# Breakout2v2.net
KiCad netlist of a schematic drawn in EAGLE
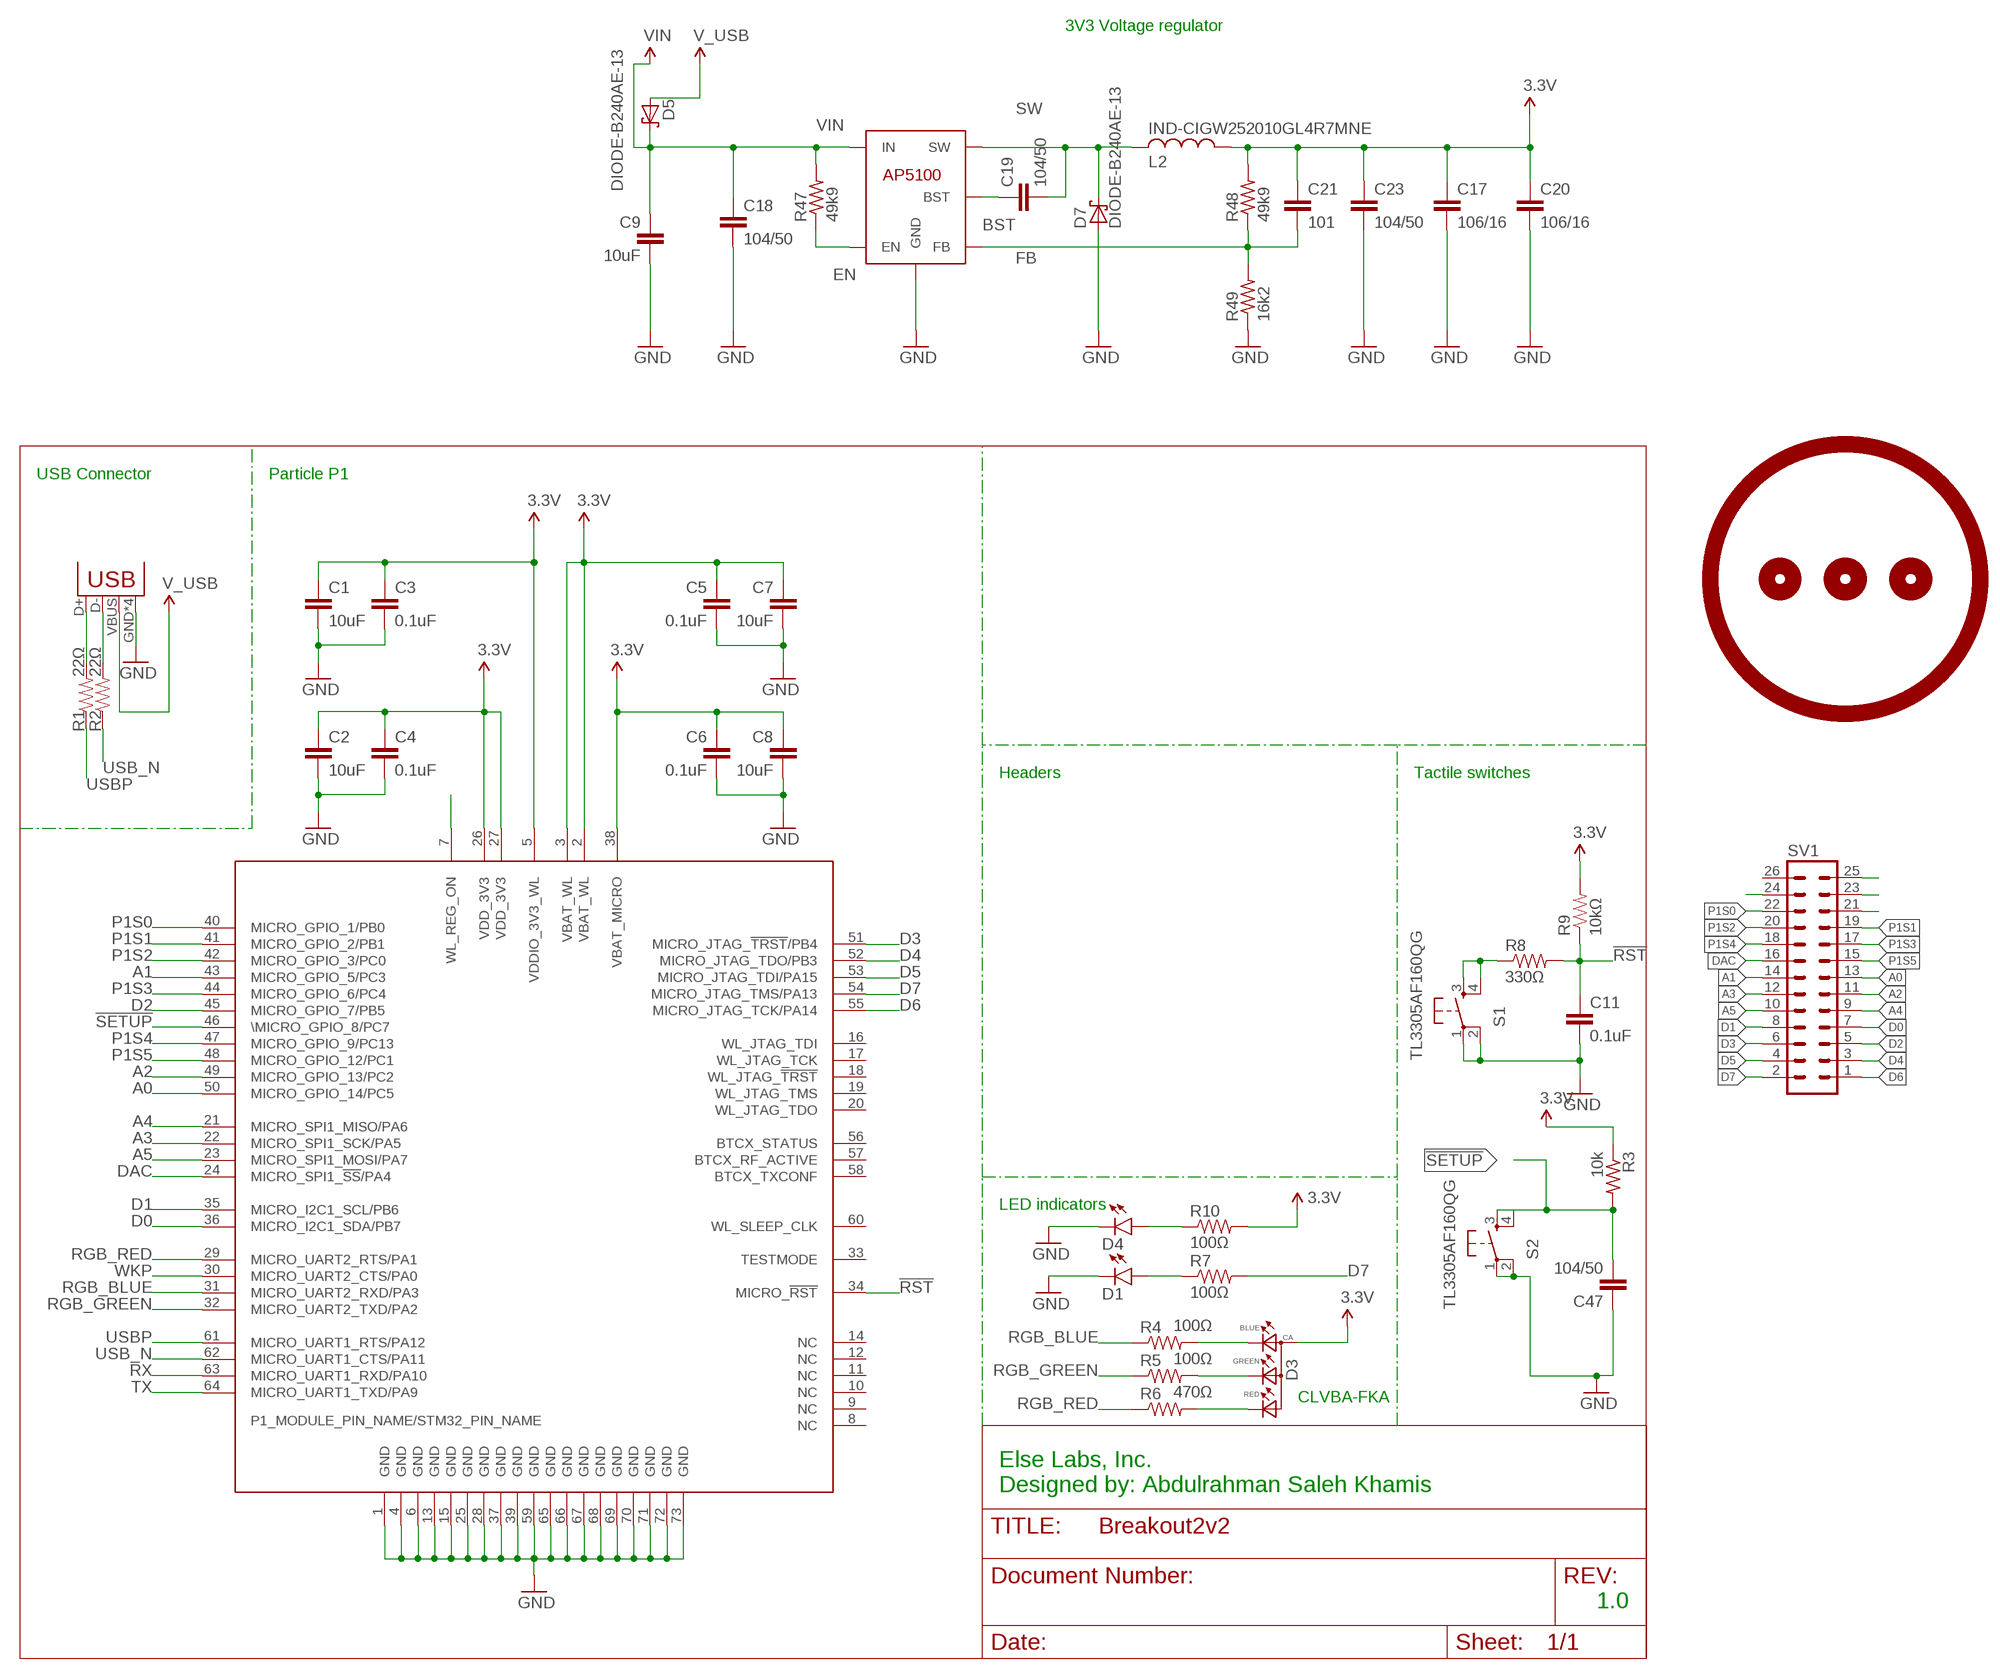
[diagram p0: schematic, sheet 1]

(export (version "E")
  (design (tool "Eeschema 10.0.6"))
  (components
    (comp (ref "C1")
      (value "10uF")
      (footprint "eagle-import:0805")
      (libsource (lib "eagle-import") (part "CAP0805"))
    )
    (comp (ref "C2")
      (value "10uF")
      (footprint "eagle-import:0805")
      (libsource (lib "eagle-import") (part "CAP0805"))
    )
    (comp (ref "C3")
      (value "0.1uF")
      (footprint "eagle-import:0805")
      (libsource (lib "eagle-import") (part "CAP0805"))
    )
    (comp (ref "C4")
      (value "0.1uF")
      (footprint "eagle-import:0805")
      (libsource (lib "eagle-import") (part "CAP0805"))
    )
    (comp (ref "C5")
      (value "0.1uF")
      (footprint "eagle-import:0805")
      (libsource (lib "eagle-import") (part "CAP0805"))
    )
    (comp (ref "C6")
      (value "0.1uF")
      (footprint "eagle-import:0805")
      (libsource (lib "eagle-import") (part "CAP0805"))
    )
    (comp (ref "C7")
      (value "10uF")
      (footprint "eagle-import:0805")
      (libsource (lib "eagle-import") (part "CAP0805"))
    )
    (comp (ref "C8")
      (value "10uF")
      (footprint "eagle-import:0805")
      (libsource (lib "eagle-import") (part "CAP0805"))
    )
    (comp (ref "C9")
      (value "10uF")
      (footprint "eagle-import:0805")
      (libsource (lib "eagle-import") (part "CAP0805"))
    )
    (comp (ref "C11")
      (value "0.1uF")
      (footprint "eagle-import:0805")
      (libsource (lib "eagle-import") (part "CAP0805"))
    )
    (comp (ref "C17")
      (value "106/16")
      (footprint "eagle-import:C0805")
      (libsource (lib "eagle-import") (part "C-EUC0805"))
    )
    (comp (ref "C18")
      (value "104/50")
      (footprint "eagle-import:C0603")
      (libsource (lib "eagle-import") (part "C-EUC0603"))
    )
    (comp (ref "C19")
      (value "104/50")
      (footprint "eagle-import:C0603")
      (libsource (lib "eagle-import") (part "C-EUC0603"))
    )
    (comp (ref "C20")
      (value "106/16")
      (footprint "eagle-import:C0805")
      (libsource (lib "eagle-import") (part "C-EUC0805"))
    )
    (comp (ref "C21")
      (value "101")
      (footprint "eagle-import:C0603")
      (libsource (lib "eagle-import") (part "C-EUC0603"))
    )
    (comp (ref "C23")
      (value "104/50")
      (footprint "eagle-import:C0603")
      (libsource (lib "eagle-import") (part "C-EUC0603"))
    )
    (comp (ref "C47")
      (value "104/50")
      (footprint "eagle-import:C0603")
      (libsource (lib "eagle-import") (part "C-EUC0603"))
    )
    (comp (ref "D1")
      (value "LED0603")
      (footprint "eagle-import:LED-0603")
      (libsource (lib "eagle-import") (part "LED0603"))
    )
    (comp (ref "D3")
      (value "CLVBA-FKAPLCC")
      (footprint "eagle-import:4-PLCC")
      (libsource (lib "eagle-import") (part "CLVBA-FKAPLCC"))
    )
    (comp (ref "D4")
      (value "LED0603")
      (footprint "eagle-import:LED-0603")
      (libsource (lib "eagle-import") (part "LED0603"))
    )
    (comp (ref "D5")
      (value "DIODE-B240AE-13")
      (footprint "eagle-import:DO-214AC")
      (libsource (lib "eagle-import") (part "DIODE-B240AE-13"))
    )
    (comp (ref "D7")
      (value "DIODE-B240AE-13")
      (footprint "eagle-import:DO-214AC")
      (libsource (lib "eagle-import") (part "DIODE-B240AE-13"))
    )
    (comp (ref "IC5")
      (value "SMSP-BUCK-AP5100")
      (footprint "eagle-import:SOT23-6")
      (libsource (lib "eagle-import") (part "SMSP-BUCK-AP5100"))
    )
    (comp (ref "JP1")
      (value "USBUSB-MICROB-SLOT-HOLE")
      (footprint "eagle-import:USB-MICROB-SLOT-HOLE")
      (libsource (lib "eagle-import") (part "USBUSB-MICROB-SLOT-HOLE"))
    )
    (comp (ref "L2")
      (value "IND-CIGW252010GL4R7MNE")
      (footprint "eagle-import:L2520")
      (libsource (lib "eagle-import") (part "IND-CIGW252010GL4R7MNE"))
    )
    (comp (ref "R1")
      (value "22Ω")
      (footprint "eagle-import:0805")
      (libsource (lib "eagle-import") (part "RESISTOR0805-RES"))
    )
    (comp (ref "R2")
      (value "22Ω")
      (footprint "eagle-import:0805")
      (libsource (lib "eagle-import") (part "RESISTOR0805-RES"))
    )
    (comp (ref "R3")
      (value "10k")
      (footprint "eagle-import:R0603")
      (libsource (lib "eagle-import") (part "R-US_R0603"))
    )
    (comp (ref "R4")
      (value "100Ω")
      (footprint "eagle-import:0805")
      (libsource (lib "eagle-import") (part "RESISTOR0805-RES"))
    )
    (comp (ref "R5")
      (value "100Ω")
      (footprint "eagle-import:0805")
      (libsource (lib "eagle-import") (part "RESISTOR0805-RES"))
    )
    (comp (ref "R6")
      (value "470Ω")
      (footprint "eagle-import:0805")
      (libsource (lib "eagle-import") (part "RESISTOR0805-RES"))
    )
    (comp (ref "R7")
      (value "100Ω")
      (footprint "eagle-import:0805")
      (libsource (lib "eagle-import") (part "RESISTOR0805-RES"))
    )
    (comp (ref "R8")
      (value "330Ω")
      (footprint "eagle-import:0805")
      (libsource (lib "eagle-import") (part "RESISTOR0805-RES"))
    )
    (comp (ref "R9")
      (value "10kΩ")
      (footprint "eagle-import:0805")
      (libsource (lib "eagle-import") (part "RESISTOR0805-RES"))
    )
    (comp (ref "R10")
      (value "100Ω")
      (footprint "eagle-import:0805")
      (libsource (lib "eagle-import") (part "RESISTOR0805-RES"))
    )
    (comp (ref "R47")
      (value "49k9")
      (footprint "eagle-import:R0603")
      (libsource (lib "eagle-import") (part "R-US_R0603"))
    )
    (comp (ref "R48")
      (value "49k9")
      (footprint "eagle-import:R0603")
      (libsource (lib "eagle-import") (part "R-US_R0603"))
    )
    (comp (ref "R49")
      (value "16k2")
      (footprint "eagle-import:R0603")
      (libsource (lib "eagle-import") (part "R-US_R0603"))
    )
    (comp (ref "S1")
      (value "TL3305AF160QG")
      (footprint "eagle-import:TACTILE_SWITCH_SMD_4.5X4.5MM")
      (libsource (lib "eagle-import") (part "SWITCH-MOMENTARY-4.5MX4.5M"))
    )
    (comp (ref "S2")
      (value "TL3305AF160QG")
      (footprint "eagle-import:TACTILE_SWITCH_SMD_4.5X4.5MM")
      (libsource (lib "eagle-import") (part "SWITCH-MOMENTARY-4.5MX4.5M"))
    )
    (comp (ref "SV1")
      (value "MA13-2")
      (footprint "eagle-import:MA13-2")
      (libsource (lib "eagle-import") (part "MA13-2"))
    )
    (comp (ref "U$1")
      (value "LOGO")
      (footprint "eagle-import:LOGO")
      (libsource (lib "eagle-import") (part "LOGO"))
    )
    (comp (ref "UC1")
      (value "P1")
      (footprint "eagle-import:WM-N-BM-14")
      (libsource (lib "eagle-import") (part "P1"))
    )
  )
  (nets
    (net (code "1") (name "/BST") (class "Default")
      (node (ref "C19") (pin "1") (pinfunction "1_1") (pintype "passive"))
      (node (ref "IC5") (pin "1") (pinfunction "BST_1") (pintype "bidirectional"))
    )
    (net (code "2") (name "/EN") (class "Default")
      (node (ref "IC5") (pin "4") (pinfunction "EN_4") (pintype "bidirectional"))
      (node (ref "R47") (pin "1") (pinfunction "1_1") (pintype "passive"))
    )
    (net (code "3") (name "/FB") (class "Default")
      (node (ref "C21") (pin "2") (pinfunction "2_2") (pintype "passive"))
      (node (ref "IC5") (pin "3") (pinfunction "FB_3") (pintype "bidirectional"))
      (node (ref "R48") (pin "1") (pinfunction "1_1") (pintype "passive"))
      (node (ref "R49") (pin "2") (pinfunction "2_2") (pintype "passive"))
    )
    (net (code "4") (name "/RGB_BLUE") (class "Default")
      (node (ref "R4") (pin "1") (pinfunction "1_1") (pintype "passive"))
      (node (ref "UC1") (pin "31") (pinfunction "MICRO_UART2_RXD/PA3_31") (pintype "bidirectional"))
    )
    (net (code "5") (name "/RGB_GREEN") (class "Default")
      (node (ref "R5") (pin "1") (pinfunction "1_1") (pintype "passive"))
      (node (ref "UC1") (pin "32") (pinfunction "MICRO_UART2_TXD/PA2_32") (pintype "bidirectional"))
    )
    (net (code "6") (name "/RGB_RED") (class "Default")
      (node (ref "R6") (pin "1") (pinfunction "1_1") (pintype "passive"))
      (node (ref "UC1") (pin "29") (pinfunction "MICRO_UART2_RTS/PA1_29") (pintype "bidirectional"))
    )
    (net (code "7") (name "/RX") (class "Default")
      (node (ref "UC1") (pin "63") (pinfunction "MICRO_UART1_RXD/PA10_63") (pintype "bidirectional"))
    )
    (net (code "8") (name "/SW") (class "Default")
      (node (ref "C19") (pin "2") (pinfunction "2_2") (pintype "passive"))
      (node (ref "D7") (pin "C") (pinfunction "C_C") (pintype "passive"))
      (node (ref "IC5") (pin "6") (pinfunction "SW_6") (pintype "bidirectional"))
      (node (ref "L2") (pin "P$2") (pinfunction "2_P$2") (pintype "passive"))
    )
    (net (code "9") (name "/TX") (class "Default")
      (node (ref "UC1") (pin "64") (pinfunction "MICRO_UART1_TXD/PA9_64") (pintype "bidirectional"))
    )
    (net (code "10") (name "/USBP") (class "Default")
      (node (ref "R1") (pin "1") (pinfunction "1_1") (pintype "passive"))
      (node (ref "UC1") (pin "61") (pinfunction "MICRO_UART1_RTS/PA12_61") (pintype "bidirectional"))
    )
    (net (code "11") (name "/USB_N") (class "Default")
      (node (ref "R2") (pin "1") (pinfunction "1_1") (pintype "passive"))
      (node (ref "UC1") (pin "62") (pinfunction "MICRO_UART1_CTS/PA11_62") (pintype "bidirectional"))
    )
    (net (code "12") (name "/WKP") (class "Default")
      (node (ref "UC1") (pin "30") (pinfunction "MICRO_UART2_CTS/PA0_30") (pintype "bidirectional"))
    )
    (net (code "13") (name "/~{RST}") (class "Default")
      (node (ref "C11") (pin "1") (pinfunction "1_1") (pintype "passive"))
      (node (ref "R8") (pin "2") (pinfunction "2_2") (pintype "passive"))
      (node (ref "R9") (pin "1") (pinfunction "1_1") (pintype "passive"))
      (node (ref "UC1") (pin "34") (pinfunction "MICRO_~{RST}_34") (pintype "bidirectional"))
    )
    (net (code "14") (name "/~{SETUP}") (class "Default")
      (node (ref "C47") (pin "2") (pinfunction "2_2") (pintype "passive"))
      (node (ref "R3") (pin "2") (pinfunction "2_2") (pintype "passive"))
      (node (ref "S2") (pin "3") (pinfunction "3_3") (pintype "passive"))
      (node (ref "S2") (pin "4") (pinfunction "4_4") (pintype "passive"))
      (node (ref "UC1") (pin "46") (pinfunction "\\MICRO_GPIO_8/PC7_46") (pintype "bidirectional"))
    )
    (net (code "15") (name "3.3V") (class "Default")
      (node (ref "C1") (pin "1") (pinfunction "1_1") (pintype "passive"))
      (node (ref "C17") (pin "1") (pinfunction "1_1") (pintype "passive"))
      (node (ref "C2") (pin "1") (pinfunction "1_1") (pintype "passive"))
      (node (ref "C20") (pin "1") (pinfunction "1_1") (pintype "passive"))
      (node (ref "C21") (pin "1") (pinfunction "1_1") (pintype "passive"))
      (node (ref "C23") (pin "1") (pinfunction "1_1") (pintype "passive"))
      (node (ref "C3") (pin "1") (pinfunction "1_1") (pintype "passive"))
      (node (ref "C4") (pin "1") (pinfunction "1_1") (pintype "passive"))
      (node (ref "C5") (pin "1") (pinfunction "1_1") (pintype "passive"))
      (node (ref "C6") (pin "1") (pinfunction "1_1") (pintype "passive"))
      (node (ref "C7") (pin "1") (pinfunction "1_1") (pintype "passive"))
      (node (ref "C8") (pin "1") (pinfunction "1_1") (pintype "passive"))
      (node (ref "D3") (pin "2") (pinfunction "ANODE_2") (pintype "passive"))
      (node (ref "L2") (pin "P$1") (pinfunction "1_P$1") (pintype "passive"))
      (node (ref "R10") (pin "2") (pinfunction "2_2") (pintype "passive"))
      (node (ref "R3") (pin "1") (pinfunction "1_1") (pintype "passive"))
      (node (ref "R48") (pin "2") (pinfunction "2_2") (pintype "passive"))
      (node (ref "R9") (pin "2") (pinfunction "2_2") (pintype "passive"))
      (node (ref "UC1") (pin "2") (pinfunction "VBAT_WL_2") (pintype "bidirectional"))
      (node (ref "UC1") (pin "26") (pinfunction "VDD_3V3_26") (pintype "bidirectional"))
      (node (ref "UC1") (pin "27") (pinfunction "VDD_3V3_27") (pintype "bidirectional"))
      (node (ref "UC1") (pin "3") (pinfunction "VBAT_WL_3") (pintype "bidirectional"))
      (node (ref "UC1") (pin "38") (pinfunction "VBAT_MICRO_38") (pintype "bidirectional"))
      (node (ref "UC1") (pin "5") (pinfunction "VDDIO_3V3_WL_5") (pintype "bidirectional"))
    )
    (net (code "16") (name "A0") (class "Default")
      (node (ref "SV1") (pin "13") (pinfunction "13_13") (pintype "passive"))
      (node (ref "UC1") (pin "50") (pinfunction "MICRO_GPIO_14/PC5_50") (pintype "bidirectional"))
    )
    (net (code "17") (name "A1") (class "Default")
      (node (ref "SV1") (pin "14") (pinfunction "14_14") (pintype "passive"))
      (node (ref "UC1") (pin "43") (pinfunction "MICRO_GPIO_5/PC3_43") (pintype "bidirectional"))
    )
    (net (code "18") (name "A2") (class "Default")
      (node (ref "SV1") (pin "11") (pinfunction "11_11") (pintype "passive"))
      (node (ref "UC1") (pin "49") (pinfunction "MICRO_GPIO_13/PC2_49") (pintype "bidirectional"))
    )
    (net (code "19") (name "A3") (class "Default")
      (node (ref "SV1") (pin "12") (pinfunction "12_12") (pintype "passive"))
      (node (ref "UC1") (pin "22") (pinfunction "MICRO_SPI1_SCK/PA5_22") (pintype "bidirectional"))
    )
    (net (code "20") (name "A4") (class "Default")
      (node (ref "SV1") (pin "9") (pinfunction "9_9") (pintype "passive"))
      (node (ref "UC1") (pin "21") (pinfunction "MICRO_SPI1_MISO/PA6_21") (pintype "bidirectional"))
    )
    (net (code "21") (name "A5") (class "Default")
      (node (ref "SV1") (pin "10") (pinfunction "10_10") (pintype "passive"))
      (node (ref "UC1") (pin "23") (pinfunction "MICRO_SPI1_MOSI/PA7_23") (pintype "bidirectional"))
    )
    (net (code "22") (name "D0") (class "Default")
      (node (ref "SV1") (pin "7") (pinfunction "7_7") (pintype "passive"))
      (node (ref "UC1") (pin "36") (pinfunction "MICRO_I2C1_SDA/PB7_36") (pintype "bidirectional"))
    )
    (net (code "23") (name "D1") (class "Default")
      (node (ref "SV1") (pin "8") (pinfunction "8_8") (pintype "passive"))
      (node (ref "UC1") (pin "35") (pinfunction "MICRO_I2C1_SCL/PB6_35") (pintype "bidirectional"))
    )
    (net (code "24") (name "D2") (class "Default")
      (node (ref "SV1") (pin "5") (pinfunction "5_5") (pintype "passive"))
      (node (ref "UC1") (pin "45") (pinfunction "MICRO_GPIO_7/PB5_45") (pintype "bidirectional"))
    )
    (net (code "25") (name "D3") (class "Default")
      (node (ref "SV1") (pin "6") (pinfunction "6_6") (pintype "passive"))
      (node (ref "UC1") (pin "51") (pinfunction "MICRO_JTAG_~{TRST}/PB4_51") (pintype "bidirectional"))
    )
    (net (code "26") (name "D4") (class "Default")
      (node (ref "SV1") (pin "3") (pinfunction "3_3") (pintype "passive"))
      (node (ref "UC1") (pin "52") (pinfunction "MICRO_JTAG_TDO/PB3_52") (pintype "bidirectional"))
    )
    (net (code "27") (name "D5") (class "Default")
      (node (ref "SV1") (pin "4") (pinfunction "4_4") (pintype "passive"))
      (node (ref "UC1") (pin "53") (pinfunction "MICRO_JTAG_TDI/PA15_53") (pintype "bidirectional"))
    )
    (net (code "28") (name "D6") (class "Default")
      (node (ref "SV1") (pin "1") (pinfunction "1_1") (pintype "passive"))
      (node (ref "UC1") (pin "55") (pinfunction "MICRO_JTAG_TCK/PA14_55") (pintype "bidirectional"))
    )
    (net (code "29") (name "D7") (class "Default")
      (node (ref "R7") (pin "2") (pinfunction "2_2") (pintype "passive"))
      (node (ref "SV1") (pin "2") (pinfunction "2_2") (pintype "passive"))
      (node (ref "UC1") (pin "54") (pinfunction "MICRO_JTAG_TMS/PA13_54") (pintype "bidirectional"))
    )
    (net (code "30") (name "DAC") (class "Default")
      (node (ref "SV1") (pin "16") (pinfunction "16_16") (pintype "passive"))
      (node (ref "UC1") (pin "24") (pinfunction "MICRO_SPI1_~{SS}/PA4_24") (pintype "bidirectional"))
    )
    (net (code "31") (name "GND") (class "Default")
      (node (ref "C1") (pin "2") (pinfunction "2_2") (pintype "passive"))
      (node (ref "C11") (pin "2") (pinfunction "2_2") (pintype "passive"))
      (node (ref "C17") (pin "2") (pinfunction "2_2") (pintype "passive"))
      (node (ref "C18") (pin "2") (pinfunction "2_2") (pintype "passive"))
      (node (ref "C2") (pin "2") (pinfunction "2_2") (pintype "passive"))
      (node (ref "C20") (pin "2") (pinfunction "2_2") (pintype "passive"))
      (node (ref "C23") (pin "2") (pinfunction "2_2") (pintype "passive"))
      (node (ref "C3") (pin "2") (pinfunction "2_2") (pintype "passive"))
      (node (ref "C4") (pin "2") (pinfunction "2_2") (pintype "passive"))
      (node (ref "C47") (pin "1") (pinfunction "1_1") (pintype "passive"))
      (node (ref "C5") (pin "2") (pinfunction "2_2") (pintype "passive"))
      (node (ref "C6") (pin "2") (pinfunction "2_2") (pintype "passive"))
      (node (ref "C7") (pin "2") (pinfunction "2_2") (pintype "passive"))
      (node (ref "C8") (pin "2") (pinfunction "2_2") (pintype "passive"))
      (node (ref "C9") (pin "2") (pinfunction "2_2") (pintype "passive"))
      (node (ref "D1") (pin "C") (pinfunction "C_C") (pintype "passive"))
      (node (ref "D4") (pin "C") (pinfunction "C_C") (pintype "passive"))
      (node (ref "D7") (pin "A") (pinfunction "A_A") (pintype "passive"))
      (node (ref "IC5") (pin "2") (pinfunction "GND_2") (pintype "bidirectional"))
      (node (ref "JP1") (pin "GND") (pinfunction "GND_GND") (pintype "bidirectional"))
      (node (ref "JP1") (pin "P$1") (pinfunction "GND_P$1") (pintype "bidirectional"))
      (node (ref "JP1") (pin "P$2") (pinfunction "GND_P$2") (pintype "bidirectional"))
      (node (ref "JP1") (pin "P$3") (pinfunction "GND_P$3") (pintype "bidirectional"))
      (node (ref "R49") (pin "1") (pinfunction "1_1") (pintype "passive"))
      (node (ref "S1") (pin "1") (pinfunction "1_1") (pintype "passive"))
      (node (ref "S1") (pin "2") (pinfunction "2_2") (pintype "passive"))
      (node (ref "S2") (pin "1") (pinfunction "1_1") (pintype "passive"))
      (node (ref "S2") (pin "2") (pinfunction "2_2") (pintype "passive"))
      (node (ref "UC1") (pin "1") (pinfunction "GND_1") (pintype "bidirectional"))
      (node (ref "UC1") (pin "13") (pinfunction "GND_13") (pintype "bidirectional"))
      (node (ref "UC1") (pin "15") (pinfunction "GND_15") (pintype "bidirectional"))
      (node (ref "UC1") (pin "25") (pinfunction "GND_25") (pintype "bidirectional"))
      (node (ref "UC1") (pin "28") (pinfunction "GND_28") (pintype "bidirectional"))
      (node (ref "UC1") (pin "37") (pinfunction "GND_37") (pintype "bidirectional"))
      (node (ref "UC1") (pin "39") (pinfunction "GND_39") (pintype "bidirectional"))
      (node (ref "UC1") (pin "4") (pinfunction "GND_4") (pintype "bidirectional"))
      (node (ref "UC1") (pin "59") (pinfunction "GND_59") (pintype "bidirectional"))
      (node (ref "UC1") (pin "6") (pinfunction "GND_6") (pintype "bidirectional"))
      (node (ref "UC1") (pin "65") (pinfunction "GND_65") (pintype "bidirectional"))
      (node (ref "UC1") (pin "66") (pinfunction "GND_66") (pintype "bidirectional"))
      (node (ref "UC1") (pin "67") (pinfunction "GND_67") (pintype "bidirectional"))
      (node (ref "UC1") (pin "68") (pinfunction "GND_68") (pintype "bidirectional"))
      (node (ref "UC1") (pin "69") (pinfunction "GND_69") (pintype "bidirectional"))
      (node (ref "UC1") (pin "70") (pinfunction "GND_70") (pintype "bidirectional"))
      (node (ref "UC1") (pin "71") (pinfunction "GND_71") (pintype "bidirectional"))
      (node (ref "UC1") (pin "72") (pinfunction "GND_72") (pintype "bidirectional"))
      (node (ref "UC1") (pin "73") (pinfunction "GND_73") (pintype "bidirectional"))
    )
    (net (code "32") (name "Net-(D1-PadA)") (class "Default")
      (node (ref "D1") (pin "A") (pinfunction "A_A") (pintype "passive"))
      (node (ref "R7") (pin "1") (pinfunction "1_1") (pintype "passive"))
    )
    (net (code "33") (name "Net-(D3-BLUE)") (class "Default")
      (node (ref "D3") (pin "3") (pinfunction "BLUE_3") (pintype "passive"))
      (node (ref "R4") (pin "2") (pinfunction "2_2") (pintype "passive"))
    )
    (net (code "34") (name "Net-(D3-GREEN)") (class "Default")
      (node (ref "D3") (pin "4") (pinfunction "GREEN_4") (pintype "passive"))
      (node (ref "R5") (pin "2") (pinfunction "2_2") (pintype "passive"))
    )
    (net (code "35") (name "Net-(D3-RED)") (class "Default")
      (node (ref "D3") (pin "1") (pinfunction "RED_1") (pintype "passive"))
      (node (ref "R6") (pin "2") (pinfunction "2_2") (pintype "passive"))
    )
    (net (code "36") (name "Net-(D4-PadA)") (class "Default")
      (node (ref "D4") (pin "A") (pinfunction "A_A") (pintype "passive"))
      (node (ref "R10") (pin "1") (pinfunction "1_1") (pintype "passive"))
    )
    (net (code "37") (name "Net-(JP1-PadD+)") (class "Default")
      (node (ref "JP1") (pin "D+") (pinfunction "D+_D+") (pintype "bidirectional"))
      (node (ref "R1") (pin "2") (pinfunction "2_2") (pintype "passive"))
    )
    (net (code "38") (name "Net-(JP1-PadD-)") (class "Default")
      (node (ref "JP1") (pin "D-") (pinfunction "D-_D-") (pintype "bidirectional"))
      (node (ref "R2") (pin "2") (pinfunction "2_2") (pintype "passive"))
    )
    (net (code "39") (name "Net-(R8-Pad1)") (class "Default")
      (node (ref "R8") (pin "1") (pinfunction "1_1") (pintype "passive"))
      (node (ref "S1") (pin "3") (pinfunction "3_3") (pintype "passive"))
      (node (ref "S1") (pin "4") (pinfunction "4_4") (pintype "passive"))
    )
    (net (code "40") (name "P1S0") (class "Default")
      (node (ref "SV1") (pin "22") (pinfunction "22_22") (pintype "passive"))
      (node (ref "UC1") (pin "40") (pinfunction "MICRO_GPIO_1/PB0_40") (pintype "bidirectional"))
    )
    (net (code "41") (name "P1S1") (class "Default")
      (node (ref "SV1") (pin "19") (pinfunction "19_19") (pintype "passive"))
      (node (ref "UC1") (pin "41") (pinfunction "MICRO_GPIO_2/PB1_41") (pintype "bidirectional"))
    )
    (net (code "42") (name "P1S2") (class "Default")
      (node (ref "SV1") (pin "20") (pinfunction "20_20") (pintype "passive"))
      (node (ref "UC1") (pin "42") (pinfunction "MICRO_GPIO_3/PC0_42") (pintype "bidirectional"))
    )
    (net (code "43") (name "P1S3") (class "Default")
      (node (ref "SV1") (pin "17") (pinfunction "17_17") (pintype "passive"))
      (node (ref "UC1") (pin "44") (pinfunction "MICRO_GPIO_6/PC4_44") (pintype "bidirectional"))
    )
    (net (code "44") (name "P1S4") (class "Default")
      (node (ref "SV1") (pin "18") (pinfunction "18_18") (pintype "passive"))
      (node (ref "UC1") (pin "47") (pinfunction "MICRO_GPIO_9/PC13_47") (pintype "bidirectional"))
    )
    (net (code "45") (name "P1S5") (class "Default")
      (node (ref "SV1") (pin "15") (pinfunction "15_15") (pintype "passive"))
      (node (ref "UC1") (pin "48") (pinfunction "MICRO_GPIO_12/PC1_48") (pintype "bidirectional"))
    )
    (net (code "46") (name "VIN") (class "Default")
      (node (ref "C18") (pin "1") (pinfunction "1_1") (pintype "passive"))
      (node (ref "C9") (pin "1") (pinfunction "1_1") (pintype "passive"))
      (node (ref "D5") (pin "C") (pinfunction "C_C") (pintype "passive"))
      (node (ref "IC5") (pin "5") (pinfunction "IN_5") (pintype "bidirectional"))
      (node (ref "R47") (pin "2") (pinfunction "2_2") (pintype "passive"))
    )
    (net (code "47") (name "V_USB") (class "Default")
      (node (ref "D5") (pin "A") (pinfunction "A_A") (pintype "passive"))
      (node (ref "JP1") (pin "VBUS") (pinfunction "VBUS_VBUS") (pintype "bidirectional"))
    )
    (net (code "48") (name "unconnected-(SV1-Pad21)") (class "Default")
      (node (ref "SV1") (pin "21") (pinfunction "21_21") (pintype "passive"))
    )
    (net (code "49") (name "unconnected-(SV1-Pad23)") (class "Default")
      (node (ref "SV1") (pin "23") (pinfunction "23_23") (pintype "passive"))
    )
    (net (code "50") (name "unconnected-(SV1-Pad24)") (class "Default")
      (node (ref "SV1") (pin "24") (pinfunction "24_24") (pintype "passive"))
    )
    (net (code "51") (name "unconnected-(SV1-Pad25)") (class "Default")
      (node (ref "SV1") (pin "25") (pinfunction "25_25") (pintype "passive"))
    )
    (net (code "52") (name "unconnected-(SV1-Pad26)") (class "Default")
      (node (ref "SV1") (pin "26") (pinfunction "26_26") (pintype "passive"))
    )
    (net (code "53") (name "unconnected-(UC1-BTCX_RF_ACTIVE-Pad57)") (class "Default")
      (node (ref "UC1") (pin "57") (pinfunction "BTCX_RF_ACTIVE_57") (pintype "bidirectional"))
    )
    (net (code "54") (name "unconnected-(UC1-BTCX_STATUS-Pad56)") (class "Default")
      (node (ref "UC1") (pin "56") (pinfunction "BTCX_STATUS_56") (pintype "bidirectional"))
    )
    (net (code "55") (name "unconnected-(UC1-BTCX_TXCONF-Pad58)") (class "Default")
      (node (ref "UC1") (pin "58") (pinfunction "BTCX_TXCONF_58") (pintype "bidirectional"))
    )
    (net (code "56") (name "unconnected-(UC1-NC-Pad8)") (class "Default")
      (node (ref "UC1") (pin "8") (pinfunction "NC_8") (pintype "bidirectional"))
    )
    (net (code "57") (name "unconnected-(UC1-NC-Pad9)") (class "Default")
      (node (ref "UC1") (pin "9") (pinfunction "NC_9") (pintype "bidirectional"))
    )
    (net (code "58") (name "unconnected-(UC1-NC-Pad10)") (class "Default")
      (node (ref "UC1") (pin "10") (pinfunction "NC_10") (pintype "bidirectional"))
    )
    (net (code "59") (name "unconnected-(UC1-NC-Pad11)") (class "Default")
      (node (ref "UC1") (pin "11") (pinfunction "NC_11") (pintype "bidirectional"))
    )
    (net (code "60") (name "unconnected-(UC1-NC-Pad12)") (class "Default")
      (node (ref "UC1") (pin "12") (pinfunction "NC_12") (pintype "bidirectional"))
    )
    (net (code "61") (name "unconnected-(UC1-NC-Pad14)") (class "Default")
      (node (ref "UC1") (pin "14") (pinfunction "NC_14") (pintype "bidirectional"))
    )
    (net (code "62") (name "unconnected-(UC1-TESTMODE-Pad33)") (class "Default")
      (node (ref "UC1") (pin "33") (pinfunction "TESTMODE_33") (pintype "bidirectional"))
    )
    (net (code "63") (name "unconnected-(UC1-WL_JTAG_TCK-Pad17)") (class "Default")
      (node (ref "UC1") (pin "17") (pinfunction "WL_JTAG_TCK_17") (pintype "bidirectional"))
    )
    (net (code "64") (name "unconnected-(UC1-WL_JTAG_TDI-Pad16)") (class "Default")
      (node (ref "UC1") (pin "16") (pinfunction "WL_JTAG_TDI_16") (pintype "bidirectional"))
    )
    (net (code "65") (name "unconnected-(UC1-WL_JTAG_TDO-Pad20)") (class "Default")
      (node (ref "UC1") (pin "20") (pinfunction "WL_JTAG_TDO_20") (pintype "bidirectional"))
    )
    (net (code "66") (name "unconnected-(UC1-WL_JTAG_TMS-Pad19)") (class "Default")
      (node (ref "UC1") (pin "19") (pinfunction "WL_JTAG_TMS_19") (pintype "bidirectional"))
    )
    (net (code "67") (name "unconnected-(UC1-WL_JTAG_~{TRST}-Pad18)") (class "Default")
      (node (ref "UC1") (pin "18") (pinfunction "WL_JTAG_~{TRST}_18") (pintype "bidirectional"))
    )
    (net (code "68") (name "unconnected-(UC1-WL_REG_ON-Pad7)") (class "Default")
      (node (ref "UC1") (pin "7") (pinfunction "WL_REG_ON_7") (pintype "bidirectional"))
    )
    (net (code "69") (name "unconnected-(UC1-WL_SLEEP_CLK-Pad60)") (class "Default")
      (node (ref "UC1") (pin "60") (pinfunction "WL_SLEEP_CLK_60") (pintype "bidirectional"))
    )
  )
)
